# Sensor.net
KiCad netlist of a schematic drawn in Altium Designer
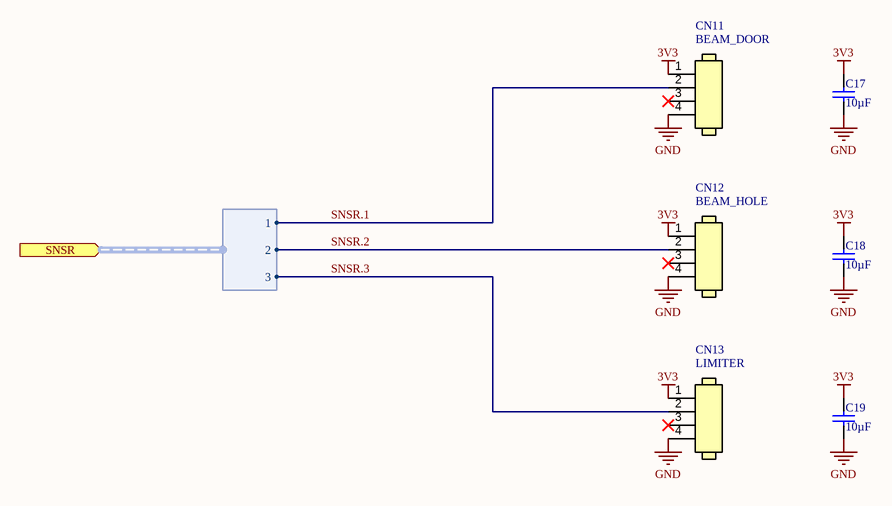
[diagram p0: Sensor.SchDoc]

(export (version "E")
  (design (tool "Eeschema 10.0.6"))
  (components
    (comp (ref "C17")
      (value "10µF")
      (footprint "CAP_CHIP_0603")
      (description "0603 Multilayer Ceramic Capacitors MLCC")
      (fields (field (name "PARTNUMBER") "CL10A106MA8NRNC") (field (name "TOLERANCE") "20%"))
      (libsource (lib "Sainsbury Wellcome Centre") (part "Cap"))
    )
    (comp (ref "C18")
      (value "10µF")
      (footprint "CAP_CHIP_0603")
      (description "0603 Multilayer Ceramic Capacitors MLCC")
      (fields (field (name "PARTNUMBER") "CL10A106MA8NRNC") (field (name "TOLERANCE") "20%"))
      (libsource (lib "Sainsbury Wellcome Centre") (part "Cap"))
    )
    (comp (ref "C19")
      (value "10µF")
      (footprint "CAP_CHIP_0603")
      (description "0603 Multilayer Ceramic Capacitors MLCC")
      (fields (field (name "PARTNUMBER") "CL10A106MA8NRNC") (field (name "TOLERANCE") "20%"))
      (libsource (lib "Sainsbury Wellcome Centre") (part "Cap"))
    )
    (comp (ref "CN11")
      (value "BEAM_DOOR")
      (footprint "MOLEX_1.25_R_DIP_4P")
      (description "Conn Shrouded Header (4 Sides) HDR 4 POS 1.25mm Solder RA Side Entry Thru-Hole PicoBlade™ Tray")
      (fields (field (name "PARTNUMBER") "53048-0410"))
      (libsource (lib "Sainsbury Wellcome Centre") (part "Wire to Board 1x4"))
    )
    (comp (ref "CN12")
      (value "BEAM_HOLE")
      (footprint "MOLEX_1.25_R_DIP_4P")
      (description "Conn Shrouded Header (4 Sides) HDR 4 POS 1.25mm Solder RA Side Entry Thru-Hole PicoBlade™ Tray")
      (fields (field (name "PARTNUMBER") "53048-0410"))
      (libsource (lib "Sainsbury Wellcome Centre") (part "Wire to Board 1x4"))
    )
    (comp (ref "CN13")
      (value "LIMITER")
      (footprint "MOLEX_1.25_R_DIP_4P")
      (description "Conn Shrouded Header (4 Sides) HDR 4 POS 1.25mm Solder RA Side Entry Thru-Hole PicoBlade™ Tray")
      (fields (field (name "PARTNUMBER") "53048-0410"))
      (libsource (lib "Sainsbury Wellcome Centre") (part "Wire to Board 1x4"))
    )
  )
  (nets
    (net (code "2") (name "/SNSR.1") (class "Default")
      (node (ref "CN11") (pin "2") (pinfunction "2_2") (pintype "passive"))
    )
    (net (code "3") (name "/SNSR.2") (class "Default")
      (node (ref "CN12") (pin "2") (pinfunction "2_2") (pintype "passive"))
    )
    (net (code "4") (name "/SNSR.3") (class "Default")
      (node (ref "CN13") (pin "2") (pinfunction "2_2") (pintype "passive"))
    )
    (net (code "6") (name "3V3") (class "Default")
      (node (ref "C17") (pin "2") (pinfunction "2_2") (pintype "passive"))
      (node (ref "C18") (pin "2") (pinfunction "2_2") (pintype "passive"))
      (node (ref "C19") (pin "2") (pinfunction "2_2") (pintype "passive"))
      (node (ref "CN11") (pin "1") (pinfunction "1_1") (pintype "passive"))
      (node (ref "CN12") (pin "1") (pinfunction "1_1") (pintype "passive"))
      (node (ref "CN13") (pin "1") (pinfunction "1_1") (pintype "passive"))
    )
    (net (code "7") (name "GND") (class "Default")
      (node (ref "C17") (pin "1") (pinfunction "1_1") (pintype "passive"))
      (node (ref "C18") (pin "1") (pinfunction "1_1") (pintype "passive"))
      (node (ref "C19") (pin "1") (pinfunction "1_1") (pintype "passive"))
      (node (ref "CN11") (pin "4") (pinfunction "4_4") (pintype "passive"))
      (node (ref "CN12") (pin "4") (pinfunction "4_4") (pintype "passive"))
      (node (ref "CN13") (pin "4") (pinfunction "4_4") (pintype "passive"))
    )
    (net (code "8") (name "unconnected-(CN11-Pad3)") (class "Default")
      (node (ref "CN11") (pin "3") (pinfunction "3_3") (pintype "passive+no_connect"))
    )
    (net (code "9") (name "unconnected-(CN12-Pad3)") (class "Default")
      (node (ref "CN12") (pin "3") (pinfunction "3_3") (pintype "passive+no_connect"))
    )
    (net (code "10") (name "unconnected-(CN13-Pad3)") (class "Default")
      (node (ref "CN13") (pin "3") (pinfunction "3_3") (pintype "passive+no_connect"))
    )
  )
)
